# working.net
KiCad netlist of a schematic drawn in EAGLE
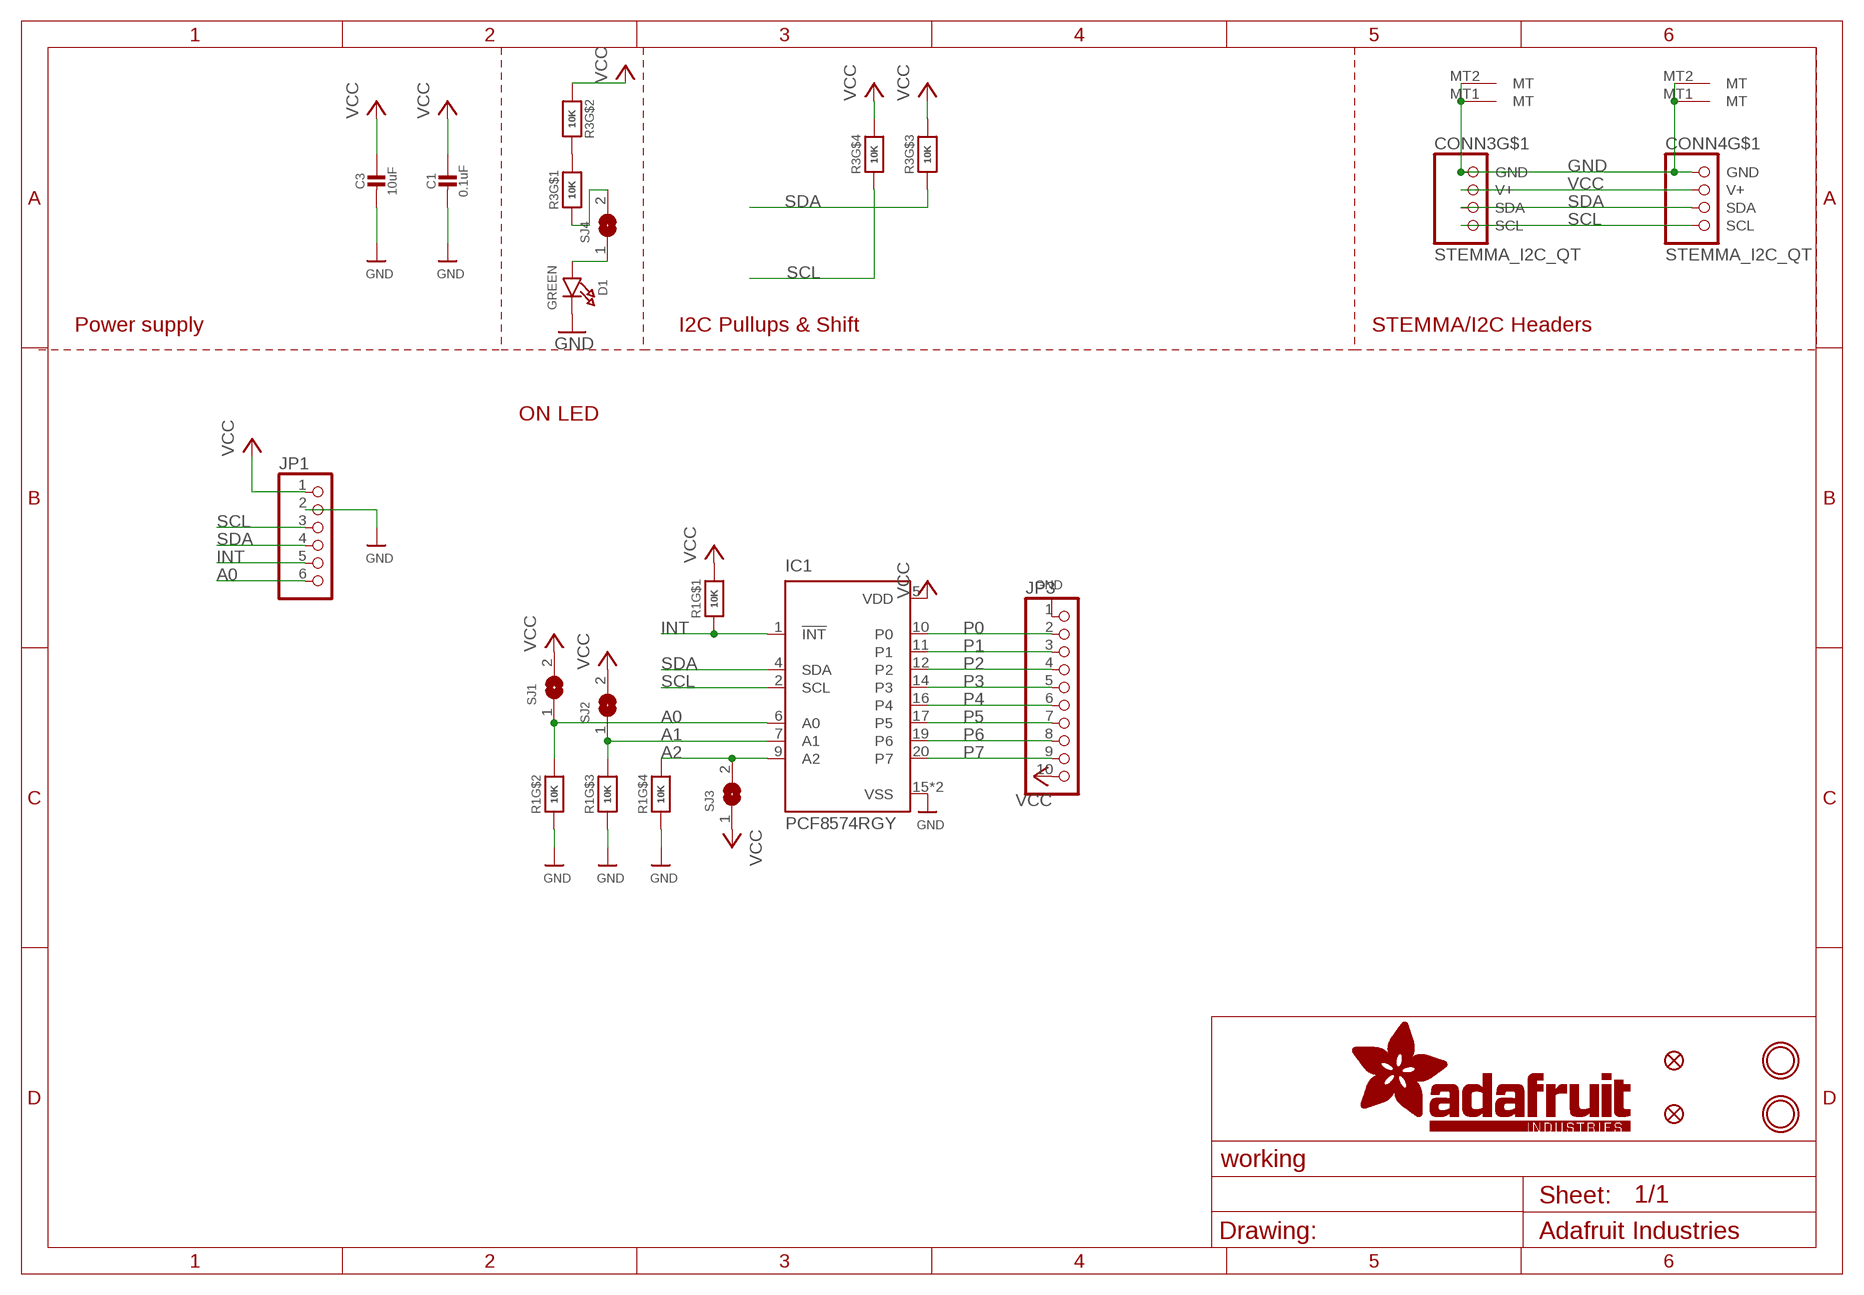
[diagram p0: schematic, sheet 1]

(export (version "E")
  (design (tool "Eeschema 10.0.6"))
  (components
    (comp (ref "C1")
      (value "0.1uF")
      (footprint "eagle-import:0603-NO")
      (libsource (lib "eagle-import") (part "CAP_CERAMIC0603_NO"))
    )
    (comp (ref "C3")
      (value "10uF")
      (footprint "eagle-import:0805-NO")
      (libsource (lib "eagle-import") (part "CAP_CERAMIC0805-NOOUTLINE"))
    )
    (comp (ref "CONN3")
      (value "STEMMA_I2C_QT")
      (footprint "eagle-import:JST_SH4")
      (libsource (lib "eagle-import") (part "STEMMA_I2C_QT"))
    )
    (comp (ref "CONN4")
      (value "STEMMA_I2C_QT")
      (footprint "eagle-import:JST_SH4")
      (libsource (lib "eagle-import") (part "STEMMA_I2C_QT"))
    )
    (comp (ref "D1")
      (value "GREEN")
      (footprint "eagle-import:CHIPLED_0603_NOOUTLINE")
      (libsource (lib "eagle-import") (part "LED0603_NOOUTLINE"))
    )
    (comp (ref "FID3")
      (value "FIDUCIAL_1MM")
      (footprint "eagle-import:FIDUCIAL_1MM")
      (libsource (lib "eagle-import") (part "FIDUCIAL_1MM"))
    )
    (comp (ref "FID4")
      (value "FIDUCIAL_1MM")
      (footprint "eagle-import:FIDUCIAL_1MM")
      (libsource (lib "eagle-import") (part "FIDUCIAL_1MM"))
    )
    (comp (ref "IC1")
      (value "PCF8574RGY")
      (footprint "eagle-import:VQFN20_3.5X4.5")
      (libsource (lib "eagle-import") (part "PCF8574RGY"))
    )
    (comp (ref "JP1")
      (value "HEADER-1X670MIL")
      (footprint "eagle-import:1X06_ROUND_70")
      (libsource (lib "eagle-import") (part "HEADER-1X670MIL"))
    )
    (comp (ref "JP3")
      (value "HEADER-1X1070MIL")
      (footprint "eagle-import:1X10_ROUND70")
      (libsource (lib "eagle-import") (part "HEADER-1X1070MIL"))
    )
    (comp (ref "R1")
      (value "10K")
      (footprint "eagle-import:RESPACK_4X0603")
      (libsource (lib "eagle-import") (part "RESISTOR_4PACK"))
    )
    (comp (ref "R3")
      (value "10K")
      (footprint "eagle-import:RESPACK_4X0603")
      (libsource (lib "eagle-import") (part "RESISTOR_4PACK"))
    )
    (comp (ref "SJ1")
      (value "SOLDERJUMPER")
      (footprint "eagle-import:SOLDERJUMPER_ARROW_NOPASTE")
      (libsource (lib "eagle-import") (part "SOLDERJUMPER"))
    )
    (comp (ref "SJ2")
      (value "SOLDERJUMPER")
      (footprint "eagle-import:SOLDERJUMPER_ARROW_NOPASTE")
      (libsource (lib "eagle-import") (part "SOLDERJUMPER"))
    )
    (comp (ref "SJ3")
      (value "SOLDERJUMPER")
      (footprint "eagle-import:SOLDERJUMPER_ARROW_NOPASTE")
      (libsource (lib "eagle-import") (part "SOLDERJUMPER"))
    )
    (comp (ref "SJ4")
      (value "SOLDERJUMPERCLOSED")
      (footprint "eagle-import:SOLDERJUMPER_CLOSEDWIRE")
      (libsource (lib "eagle-import") (part "SOLDERJUMPERCLOSED"))
    )
    (comp (ref "U$19")
      (value "MOUNTINGHOLE2.5")
      (footprint "eagle-import:MOUNTINGHOLE_2.5_PLATED")
      (libsource (lib "eagle-import") (part "MOUNTINGHOLE2.5"))
    )
    (comp (ref "U$21")
      (value "MOUNTINGHOLE2.5")
      (footprint "eagle-import:MOUNTINGHOLE_2.5_PLATED")
      (libsource (lib "eagle-import") (part "MOUNTINGHOLE2.5"))
    )
  )
  (nets
    (net (code "1") (name "/A0") (class "Default")
      (node (ref "IC1") (pin "6") (pinfunction "A0_6") (pintype "input"))
      (node (ref "JP1") (pin "6") (pinfunction "6_6") (pintype "passive"))
      (node (ref "R1") (pin "7") (pinfunction "2_7") (pintype "passive"))
      (node (ref "SJ1") (pin "1") (pinfunction "1_1") (pintype "passive"))
    )
    (net (code "2") (name "/A1") (class "Default")
      (node (ref "IC1") (pin "7") (pinfunction "A1_7") (pintype "input"))
      (node (ref "R1") (pin "6") (pinfunction "2_6") (pintype "passive"))
      (node (ref "SJ2") (pin "1") (pinfunction "1_1") (pintype "passive"))
    )
    (net (code "3") (name "/A2") (class "Default")
      (node (ref "IC1") (pin "9") (pinfunction "A2_9") (pintype "input"))
      (node (ref "R1") (pin "5") (pinfunction "2_5") (pintype "passive"))
      (node (ref "SJ3") (pin "2") (pinfunction "2_2") (pintype "passive"))
    )
    (net (code "4") (name "/INT") (class "Default")
      (node (ref "IC1") (pin "1") (pinfunction "~{INT}_1") (pintype "output"))
      (node (ref "JP1") (pin "5") (pinfunction "5_5") (pintype "passive"))
      (node (ref "R1") (pin "1") (pinfunction "1_1") (pintype "passive"))
    )
    (net (code "5") (name "/P0") (class "Default")
      (node (ref "IC1") (pin "10") (pinfunction "P0_10") (pintype "bidirectional"))
      (node (ref "JP3") (pin "2") (pinfunction "2_2") (pintype "passive"))
    )
    (net (code "6") (name "/P1") (class "Default")
      (node (ref "IC1") (pin "11") (pinfunction "P1_11") (pintype "bidirectional"))
      (node (ref "JP3") (pin "3") (pinfunction "3_3") (pintype "passive"))
    )
    (net (code "7") (name "/P2") (class "Default")
      (node (ref "IC1") (pin "12") (pinfunction "P2_12") (pintype "bidirectional"))
      (node (ref "JP3") (pin "4") (pinfunction "4_4") (pintype "passive"))
    )
    (net (code "8") (name "/P3") (class "Default")
      (node (ref "IC1") (pin "14") (pinfunction "P3_14") (pintype "bidirectional"))
      (node (ref "JP3") (pin "5") (pinfunction "5_5") (pintype "passive"))
    )
    (net (code "9") (name "/P4") (class "Default")
      (node (ref "IC1") (pin "16") (pinfunction "P4_16") (pintype "bidirectional"))
      (node (ref "JP3") (pin "6") (pinfunction "6_6") (pintype "passive"))
    )
    (net (code "10") (name "/P5") (class "Default")
      (node (ref "IC1") (pin "17") (pinfunction "P5_17") (pintype "bidirectional"))
      (node (ref "JP3") (pin "7") (pinfunction "7_7") (pintype "passive"))
    )
    (net (code "11") (name "/P6") (class "Default")
      (node (ref "IC1") (pin "19") (pinfunction "P6_19") (pintype "bidirectional"))
      (node (ref "JP3") (pin "8") (pinfunction "8_8") (pintype "passive"))
    )
    (net (code "12") (name "/P7") (class "Default")
      (node (ref "IC1") (pin "20") (pinfunction "P7_20") (pintype "bidirectional"))
      (node (ref "JP3") (pin "9") (pinfunction "9_9") (pintype "passive"))
    )
    (net (code "13") (name "/SCL") (class "Default")
      (node (ref "CONN3") (pin "4") (pinfunction "SCL_4") (pintype "passive"))
      (node (ref "CONN4") (pin "4") (pinfunction "SCL_4") (pintype "passive"))
      (node (ref "IC1") (pin "2") (pinfunction "SCL_2") (pintype "input"))
      (node (ref "JP1") (pin "3") (pinfunction "3_3") (pintype "passive"))
      (node (ref "R3") (pin "4") (pinfunction "1_4") (pintype "passive"))
    )
    (net (code "14") (name "/SDA") (class "Default")
      (node (ref "CONN3") (pin "3") (pinfunction "SDA_3") (pintype "passive"))
      (node (ref "CONN4") (pin "3") (pinfunction "SDA_3") (pintype "passive"))
      (node (ref "IC1") (pin "4") (pinfunction "SDA_4") (pintype "bidirectional"))
      (node (ref "JP1") (pin "4") (pinfunction "4_4") (pintype "passive"))
      (node (ref "R3") (pin "3") (pinfunction "1_3") (pintype "passive"))
    )
    (net (code "15") (name "GND") (class "Default")
      (node (ref "C1") (pin "2") (pinfunction "2_2") (pintype "passive"))
      (node (ref "C3") (pin "2") (pinfunction "2_2") (pintype "passive"))
      (node (ref "CONN3") (pin "1") (pinfunction "GND_1") (pintype "passive"))
      (node (ref "CONN3") (pin "MT1") (pinfunction "MT_MT1") (pintype "bidirectional"))
      (node (ref "CONN3") (pin "MT2") (pinfunction "MT_MT2") (pintype "bidirectional"))
      (node (ref "CONN4") (pin "1") (pinfunction "GND_1") (pintype "passive"))
      (node (ref "CONN4") (pin "MT1") (pinfunction "MT_MT1") (pintype "bidirectional"))
      (node (ref "CONN4") (pin "MT2") (pinfunction "MT_MT2") (pintype "bidirectional"))
      (node (ref "D1") (pin "C") (pinfunction "C_C") (pintype "passive"))
      (node (ref "IC1") (pin "15") (pinfunction "VSS_15") (pintype "power_in"))
      (node (ref "IC1") (pin "21") (pinfunction "VSS_21") (pintype "power_in"))
      (node (ref "JP1") (pin "2") (pinfunction "2_2") (pintype "passive"))
      (node (ref "JP3") (pin "1") (pinfunction "1_1") (pintype "passive"))
      (node (ref "R1") (pin "2") (pinfunction "1_2") (pintype "passive"))
      (node (ref "R1") (pin "3") (pinfunction "1_3") (pintype "passive"))
      (node (ref "R1") (pin "4") (pinfunction "1_4") (pintype "passive"))
    )
    (net (code "16") (name "Net-(D1-PadA)") (class "Default")
      (node (ref "D1") (pin "A") (pinfunction "A_A") (pintype "passive"))
      (node (ref "SJ4") (pin "1") (pinfunction "1_1") (pintype "passive"))
    )
    (net (code "17") (name "Net-(R3-Pad1)") (class "Default")
      (node (ref "R3") (pin "1") (pinfunction "1_1") (pintype "passive"))
      (node (ref "SJ4") (pin "2") (pinfunction "2_2") (pintype "passive"))
    )
    (net (code "18") (name "Net-(R3A-2)") (class "Default")
      (node (ref "R3") (pin "7") (pinfunction "2_7") (pintype "passive"))
      (node (ref "R3") (pin "8") (pinfunction "2_8") (pintype "passive"))
    )
    (net (code "19") (name "VCC") (class "Default")
      (node (ref "C1") (pin "1") (pinfunction "1_1") (pintype "passive"))
      (node (ref "C3") (pin "1") (pinfunction "1_1") (pintype "passive"))
      (node (ref "CONN3") (pin "2") (pinfunction "V+_2") (pintype "passive"))
      (node (ref "CONN4") (pin "2") (pinfunction "V+_2") (pintype "passive"))
      (node (ref "IC1") (pin "5") (pinfunction "VDD_5") (pintype "power_in"))
      (node (ref "JP1") (pin "1") (pinfunction "1_1") (pintype "passive"))
      (node (ref "JP3") (pin "10") (pinfunction "10_10") (pintype "passive"))
      (node (ref "R1") (pin "8") (pinfunction "2_8") (pintype "passive"))
      (node (ref "R3") (pin "2") (pinfunction "1_2") (pintype "passive"))
      (node (ref "R3") (pin "5") (pinfunction "2_5") (pintype "passive"))
      (node (ref "R3") (pin "6") (pinfunction "2_6") (pintype "passive"))
      (node (ref "SJ1") (pin "2") (pinfunction "2_2") (pintype "passive"))
      (node (ref "SJ2") (pin "2") (pinfunction "2_2") (pintype "passive"))
      (node (ref "SJ3") (pin "1") (pinfunction "1_1") (pintype "passive"))
    )
  )
)
